# a78-simple-epi.net
KiCad netlist of a schematic drawn in EAGLE
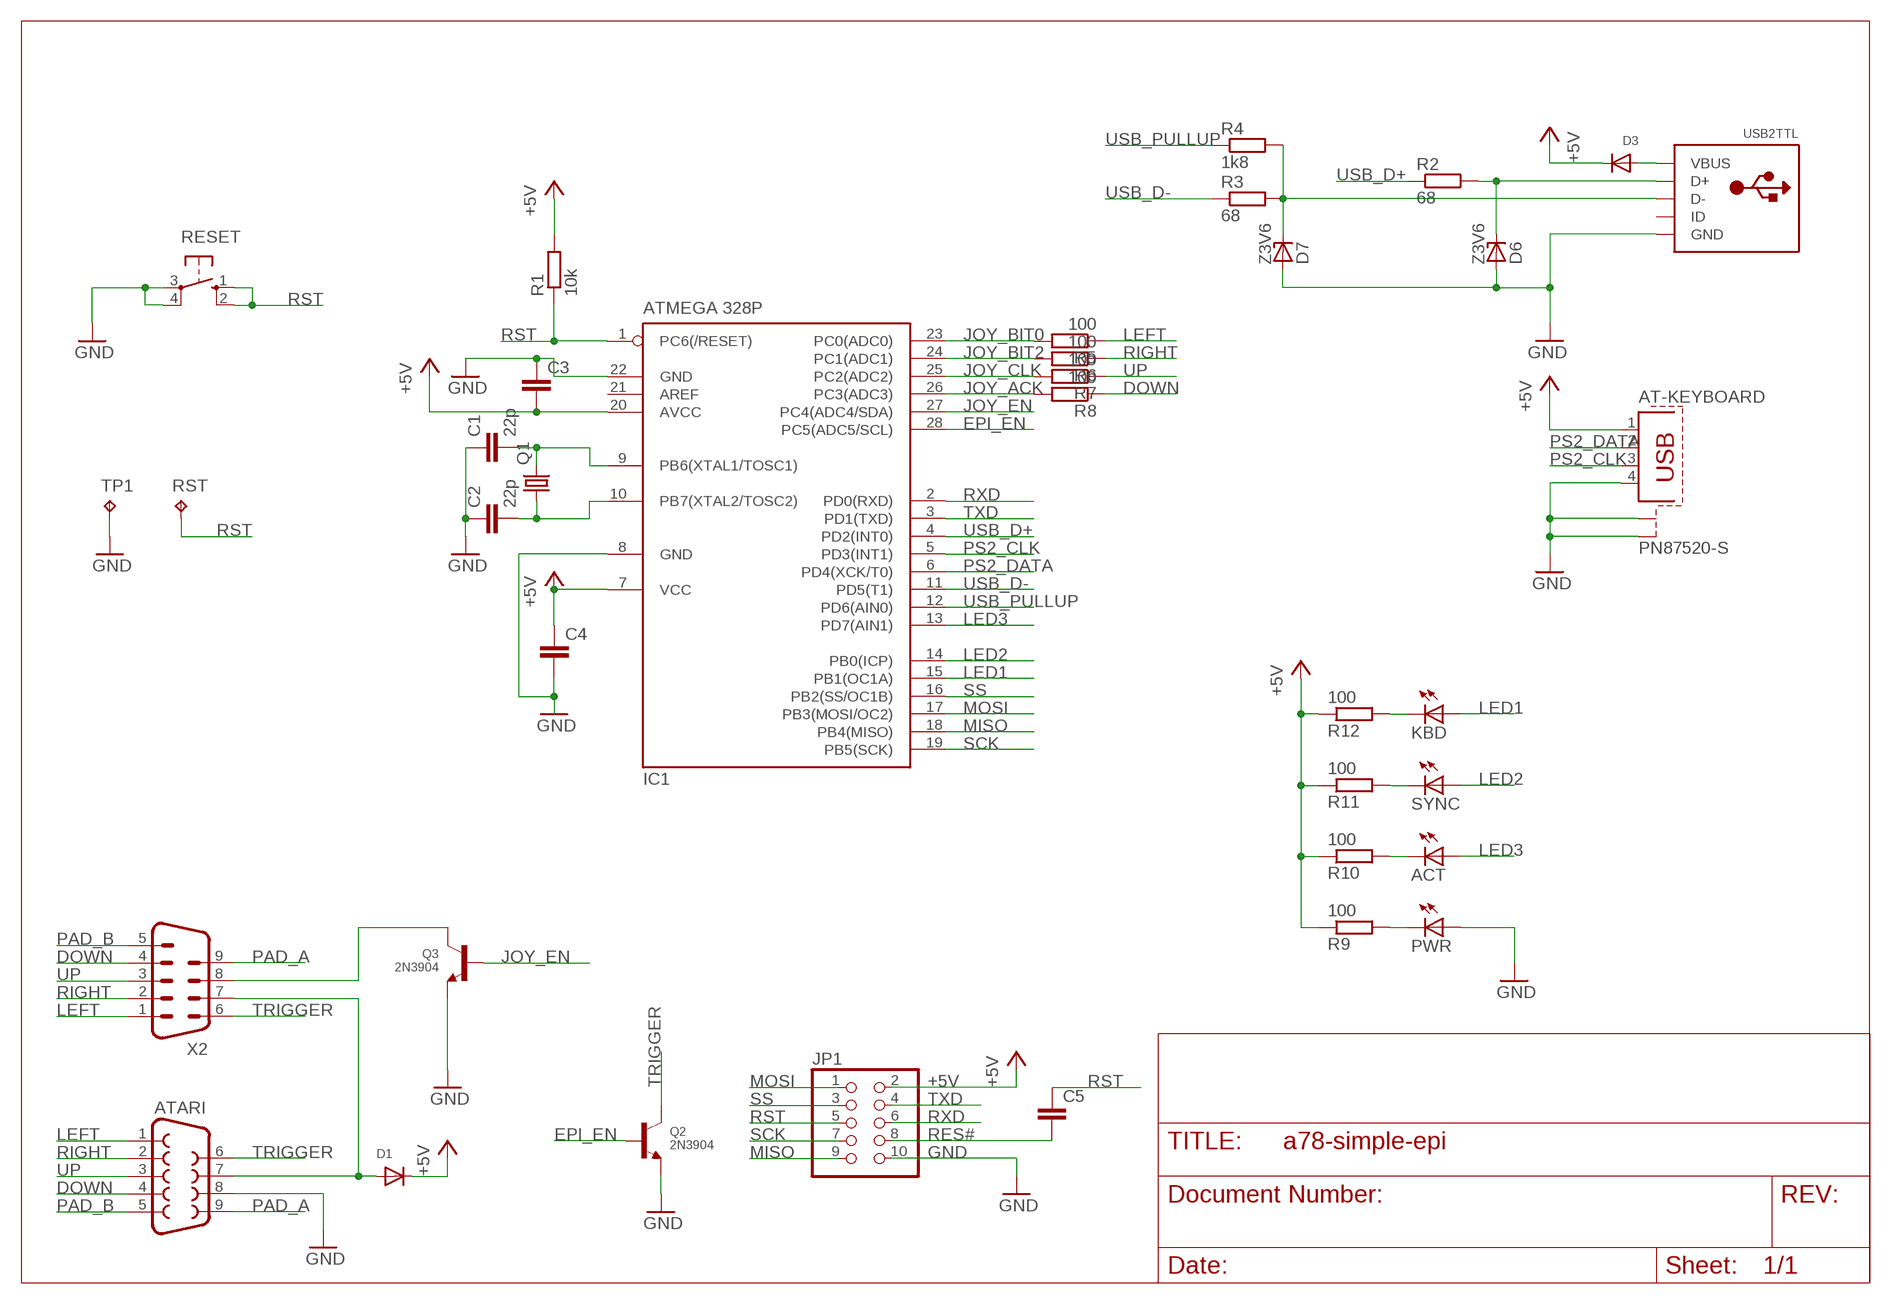
[diagram p0: schematic, sheet 1]

(export (version "E")
  (design (tool "Eeschema 10.0.6"))
  (components
    (comp (ref "ACT")
      (value "LED3MM")
      (footprint "eagle-import:LED3MM")
      (libsource (lib "eagle-import") (part "LED3MM"))
    )
    (comp (ref "AT-KEYBOARD")
      (value "PN87520-S")
      (footprint "eagle-import:PN87520-S")
      (libsource (lib "eagle-import") (part "PN87520-S"))
    )
    (comp (ref "ATARI")
      (value "F09D")
      (footprint "eagle-import:F09D")
      (libsource (lib "eagle-import") (part "F09D"))
    )
    (comp (ref "C1")
      (value "22p")
      (footprint "eagle-import:C0603")
      (libsource (lib "eagle-import") (part "C-EUC0603"))
    )
    (comp (ref "C2")
      (value "22p")
      (footprint "eagle-import:C0603")
      (libsource (lib "eagle-import") (part "C-EUC0603"))
    )
    (comp (ref "C3")
      (value "C-EUC0603")
      (footprint "eagle-import:C0603")
      (libsource (lib "eagle-import") (part "C-EUC0603"))
    )
    (comp (ref "C4")
      (value "C-EUC0603")
      (footprint "eagle-import:C0603")
      (libsource (lib "eagle-import") (part "C-EUC0603"))
    )
    (comp (ref "C5")
      (value "C-EUC0603")
      (footprint "eagle-import:C0603")
      (libsource (lib "eagle-import") (part "C-EUC0603"))
    )
    (comp (ref "D1")
      (value "DIODESOD-323F")
      (footprint "eagle-import:SOD-323F")
      (libsource (lib "eagle-import") (part "DIODESOD-323F"))
    )
    (comp (ref "D3")
      (value "DIODESOD-323F")
      (footprint "eagle-import:SOD-323F")
      (libsource (lib "eagle-import") (part "DIODESOD-323F"))
    )
    (comp (ref "D6")
      (value "Z3V6")
      (footprint "eagle-import:SOT23")
      (libsource (lib "eagle-import") (part "ZENER-DIODESOT23"))
    )
    (comp (ref "D7")
      (value "Z3V6")
      (footprint "eagle-import:SOT23")
      (libsource (lib "eagle-import") (part "ZENER-DIODESOT23"))
    )
    (comp (ref "IC1")
      (value "ATMEGA 328P")
      (footprint "eagle-import:DIL28-3")
      (libsource (lib "eagle-import") (part "MEGA8-P"))
    )
    (comp (ref "JP1")
      (value "PINHD-2X5")
      (footprint "eagle-import:2X05")
      (libsource (lib "eagle-import") (part "PINHD-2X5"))
    )
    (comp (ref "KBD")
      (value "LED3MM")
      (footprint "eagle-import:LED3MM")
      (libsource (lib "eagle-import") (part "LED3MM"))
    )
    (comp (ref "PWR")
      (value "LED3MM")
      (footprint "eagle-import:LED3MM")
      (libsource (lib "eagle-import") (part "LED3MM"))
    )
    (comp (ref "Q1")
      (value "CRYSTALHC49S")
      (footprint "eagle-import:HC49S")
      (libsource (lib "eagle-import") (part "CRYSTALHC49S"))
    )
    (comp (ref "Q2")
      (value "2N3904")
      (footprint "eagle-import:SOT23-R")
      (libsource (lib "eagle-import") (part "TRANSISTOR_NPN"))
    )
    (comp (ref "Q3")
      (value "2N3904")
      (footprint "eagle-import:SOT23-R")
      (libsource (lib "eagle-import") (part "TRANSISTOR_NPN"))
    )
    (comp (ref "R1")
      (value "10k")
      (footprint "eagle-import:R0603")
      (libsource (lib "eagle-import") (part "R-EU_R0603"))
    )
    (comp (ref "R2")
      (value "68")
      (footprint "eagle-import:R0603")
      (libsource (lib "eagle-import") (part "R-EU_R0603"))
    )
    (comp (ref "R3")
      (value "68")
      (footprint "eagle-import:R0603")
      (libsource (lib "eagle-import") (part "R-EU_R0603"))
    )
    (comp (ref "R4")
      (value "1k8")
      (footprint "eagle-import:R0603")
      (libsource (lib "eagle-import") (part "R-EU_R0603"))
    )
    (comp (ref "R5")
      (value "100")
      (footprint "eagle-import:R0603")
      (libsource (lib "eagle-import") (part "R-EU_R0603"))
    )
    (comp (ref "R6")
      (value "100")
      (footprint "eagle-import:R0603")
      (libsource (lib "eagle-import") (part "R-EU_R0603"))
    )
    (comp (ref "R7")
      (value "100")
      (footprint "eagle-import:R0603")
      (libsource (lib "eagle-import") (part "R-EU_R0603"))
    )
    (comp (ref "R8")
      (value "100")
      (footprint "eagle-import:R0603")
      (libsource (lib "eagle-import") (part "R-EU_R0603"))
    )
    (comp (ref "R9")
      (value "100")
      (footprint "eagle-import:R0603")
      (libsource (lib "eagle-import") (part "R-EU_R0603"))
    )
    (comp (ref "R10")
      (value "100")
      (footprint "eagle-import:R0603")
      (libsource (lib "eagle-import") (part "R-EU_R0603"))
    )
    (comp (ref "R11")
      (value "100")
      (footprint "eagle-import:R0603")
      (libsource (lib "eagle-import") (part "R-EU_R0603"))
    )
    (comp (ref "R12")
      (value "100")
      (footprint "eagle-import:R0603")
      (libsource (lib "eagle-import") (part "R-EU_R0603"))
    )
    (comp (ref "RESET")
      (value "10-XX")
      (footprint "eagle-import:B3F-10XX")
      (fields (field (name "MPN") "B3F-1000"))
      (libsource (lib "eagle-import") (part "10-XX"))
    )
    (comp (ref "RST")
      (value "TPB1,27")
      (footprint "eagle-import:B1,27")
      (libsource (lib "eagle-import") (part "TPB1,27"))
    )
    (comp (ref "SYNC")
      (value "LED3MM")
      (footprint "eagle-import:LED3MM")
      (libsource (lib "eagle-import") (part "LED3MM"))
    )
    (comp (ref "TP1")
      (value "TPB1,27")
      (footprint "eagle-import:B1,27")
      (libsource (lib "eagle-import") (part "TPB1,27"))
    )
    (comp (ref "USB2TTL")
      (value "USBMINIB")
      (footprint "eagle-import:USB-MINIB")
      (libsource (lib "eagle-import") (part "USBMINIB"))
    )
    (comp (ref "X2")
      (value "M09D")
      (footprint "eagle-import:M09D")
      (libsource (lib "eagle-import") (part "M09D"))
    )
  )
  (nets
    (net (code "1") (name "+5V") (class "Default")
      (node (ref "AT-KEYBOARD") (pin "1") (pinfunction "1_1") (pintype "passive"))
      (node (ref "C3") (pin "2") (pinfunction "2_2") (pintype "passive"))
      (node (ref "C4") (pin "1") (pinfunction "1_1") (pintype "passive"))
      (node (ref "D1") (pin "C") (pinfunction "C_C") (pintype "passive"))
      (node (ref "D3") (pin "C") (pinfunction "C_C") (pintype "passive"))
      (node (ref "IC1") (pin "20") (pinfunction "AVCC_20") (pintype "power_in"))
      (node (ref "IC1") (pin "7") (pinfunction "VCC_7") (pintype "power_in"))
      (node (ref "JP1") (pin "2") (pinfunction "2_2") (pintype "passive"))
      (node (ref "R1") (pin "2") (pinfunction "2_2") (pintype "passive"))
      (node (ref "R10") (pin "1") (pinfunction "1_1") (pintype "passive"))
      (node (ref "R11") (pin "1") (pinfunction "1_1") (pintype "passive"))
      (node (ref "R12") (pin "1") (pinfunction "1_1") (pintype "passive"))
      (node (ref "R9") (pin "1") (pinfunction "1_1") (pintype "passive"))
    )
    (net (code "2") (name "/DOWN") (class "Default")
      (node (ref "ATARI") (pin "4") (pinfunction "4_4") (pintype "passive"))
      (node (ref "R8") (pin "1") (pinfunction "1_1") (pintype "passive"))
      (node (ref "X2") (pin "4") (pinfunction "4_4") (pintype "passive"))
    )
    (net (code "3") (name "/EPI_EN") (class "Default")
      (node (ref "IC1") (pin "28") (pinfunction "PC5(ADC5/SCL)_28") (pintype "bidirectional"))
      (node (ref "Q2") (pin "1") (pinfunction "B_1") (pintype "passive"))
    )
    (net (code "4") (name "/JOY_ACK") (class "Default")
      (node (ref "IC1") (pin "26") (pinfunction "PC3(ADC3)_26") (pintype "bidirectional"))
      (node (ref "R8") (pin "2") (pinfunction "2_2") (pintype "passive"))
    )
    (net (code "5") (name "/JOY_BIT0") (class "Default")
      (node (ref "IC1") (pin "23") (pinfunction "PC0(ADC0)_23") (pintype "bidirectional"))
      (node (ref "R5") (pin "2") (pinfunction "2_2") (pintype "passive"))
    )
    (net (code "6") (name "/JOY_BIT2") (class "Default")
      (node (ref "IC1") (pin "24") (pinfunction "PC1(ADC1)_24") (pintype "bidirectional"))
      (node (ref "R6") (pin "2") (pinfunction "2_2") (pintype "passive"))
    )
    (net (code "7") (name "/JOY_CLK") (class "Default")
      (node (ref "IC1") (pin "25") (pinfunction "PC2(ADC2)_25") (pintype "bidirectional"))
      (node (ref "R7") (pin "2") (pinfunction "2_2") (pintype "passive"))
    )
    (net (code "8") (name "/JOY_EN") (class "Default")
      (node (ref "IC1") (pin "27") (pinfunction "PC4(ADC4/SDA)_27") (pintype "bidirectional"))
      (node (ref "Q3") (pin "1") (pinfunction "B_1") (pintype "passive"))
    )
    (net (code "9") (name "/LED1") (class "Default")
      (node (ref "IC1") (pin "15") (pinfunction "PB1(OC1A)_15") (pintype "bidirectional"))
      (node (ref "KBD") (pin "A") (pinfunction "A_A") (pintype "passive"))
    )
    (net (code "10") (name "/LED2") (class "Default")
      (node (ref "IC1") (pin "14") (pinfunction "PB0(ICP)_14") (pintype "bidirectional"))
      (node (ref "SYNC") (pin "A") (pinfunction "A_A") (pintype "passive"))
    )
    (net (code "11") (name "/LED3") (class "Default")
      (node (ref "ACT") (pin "A") (pinfunction "A_A") (pintype "passive"))
      (node (ref "IC1") (pin "13") (pinfunction "PD7(AIN1)_13") (pintype "bidirectional"))
    )
    (net (code "12") (name "/LEFT") (class "Default")
      (node (ref "ATARI") (pin "1") (pinfunction "1_1") (pintype "passive"))
      (node (ref "R5") (pin "1") (pinfunction "1_1") (pintype "passive"))
      (node (ref "X2") (pin "1") (pinfunction "1_1") (pintype "passive"))
    )
    (net (code "13") (name "/MISO") (class "Default")
      (node (ref "IC1") (pin "18") (pinfunction "PB4(MISO)_18") (pintype "bidirectional"))
      (node (ref "JP1") (pin "9") (pinfunction "9_9") (pintype "passive"))
    )
    (net (code "14") (name "/MOSI") (class "Default")
      (node (ref "IC1") (pin "17") (pinfunction "PB3(MOSI/OC2)_17") (pintype "bidirectional"))
      (node (ref "JP1") (pin "1") (pinfunction "1_1") (pintype "passive"))
    )
    (net (code "15") (name "/PAD_A") (class "Default")
      (node (ref "ATARI") (pin "9") (pinfunction "9_9") (pintype "passive"))
      (node (ref "X2") (pin "9") (pinfunction "9_9") (pintype "passive"))
    )
    (net (code "16") (name "/PAD_B") (class "Default")
      (node (ref "ATARI") (pin "5") (pinfunction "5_5") (pintype "passive"))
      (node (ref "X2") (pin "5") (pinfunction "5_5") (pintype "passive"))
    )
    (net (code "17") (name "/PS2_CLK") (class "Default")
      (node (ref "AT-KEYBOARD") (pin "3") (pinfunction "3_3") (pintype "passive"))
      (node (ref "IC1") (pin "5") (pinfunction "PD3(INT1)_5") (pintype "bidirectional"))
    )
    (net (code "18") (name "/PS2_DATA") (class "Default")
      (node (ref "AT-KEYBOARD") (pin "2") (pinfunction "2_2") (pintype "passive"))
      (node (ref "IC1") (pin "6") (pinfunction "PD4(XCK/T0)_6") (pintype "bidirectional"))
    )
    (net (code "19") (name "/RES#") (class "Default")
      (node (ref "C5") (pin "2") (pinfunction "2_2") (pintype "passive"))
      (node (ref "JP1") (pin "8") (pinfunction "8_8") (pintype "passive"))
    )
    (net (code "20") (name "/RIGHT") (class "Default")
      (node (ref "ATARI") (pin "2") (pinfunction "2_2") (pintype "passive"))
      (node (ref "R6") (pin "1") (pinfunction "1_1") (pintype "passive"))
      (node (ref "X2") (pin "2") (pinfunction "2_2") (pintype "passive"))
    )
    (net (code "21") (name "/RST") (class "Default")
      (node (ref "C5") (pin "1") (pinfunction "1_1") (pintype "passive"))
      (node (ref "IC1") (pin "1") (pinfunction "PC6(/RESET)_1") (pintype "bidirectional"))
      (node (ref "JP1") (pin "5") (pinfunction "5_5") (pintype "passive"))
      (node (ref "R1") (pin "1") (pinfunction "1_1") (pintype "passive"))
      (node (ref "RESET") (pin "1") (pinfunction "S_1") (pintype "passive"))
      (node (ref "RESET") (pin "2") (pinfunction "S1_2") (pintype "passive"))
      (node (ref "RST") (pin "TP") (pinfunction "TP_TP") (pintype "input"))
    )
    (net (code "22") (name "/RXD") (class "Default")
      (node (ref "IC1") (pin "2") (pinfunction "PD0(RXD)_2") (pintype "bidirectional"))
      (node (ref "JP1") (pin "6") (pinfunction "6_6") (pintype "passive"))
    )
    (net (code "23") (name "/SCK") (class "Default")
      (node (ref "IC1") (pin "19") (pinfunction "PB5(SCK)_19") (pintype "bidirectional"))
      (node (ref "JP1") (pin "7") (pinfunction "7_7") (pintype "passive"))
    )
    (net (code "24") (name "/SS") (class "Default")
      (node (ref "IC1") (pin "16") (pinfunction "PB2(SS/OC1B)_16") (pintype "bidirectional"))
      (node (ref "JP1") (pin "3") (pinfunction "3_3") (pintype "passive"))
    )
    (net (code "25") (name "/TRIGGER") (class "Default")
      (node (ref "ATARI") (pin "6") (pinfunction "6_6") (pintype "passive"))
      (node (ref "Q2") (pin "3") (pinfunction "C_3") (pintype "passive"))
      (node (ref "X2") (pin "6") (pinfunction "6_6") (pintype "passive"))
    )
    (net (code "26") (name "/TXD") (class "Default")
      (node (ref "IC1") (pin "3") (pinfunction "PD1(TXD)_3") (pintype "bidirectional"))
      (node (ref "JP1") (pin "4") (pinfunction "4_4") (pintype "passive"))
    )
    (net (code "27") (name "/UP") (class "Default")
      (node (ref "ATARI") (pin "3") (pinfunction "3_3") (pintype "passive"))
      (node (ref "R7") (pin "1") (pinfunction "1_1") (pintype "passive"))
      (node (ref "X2") (pin "3") (pinfunction "3_3") (pintype "passive"))
    )
    (net (code "28") (name "/USB_D+") (class "Default")
      (node (ref "IC1") (pin "4") (pinfunction "PD2(INT0)_4") (pintype "bidirectional"))
      (node (ref "R2") (pin "1") (pinfunction "1_1") (pintype "passive"))
    )
    (net (code "29") (name "/USB_D-") (class "Default")
      (node (ref "IC1") (pin "11") (pinfunction "PD5(T1)_11") (pintype "bidirectional"))
      (node (ref "R3") (pin "1") (pinfunction "1_1") (pintype "passive"))
    )
    (net (code "30") (name "/USB_PULLUP") (class "Default")
      (node (ref "IC1") (pin "12") (pinfunction "PD6(AIN0)_12") (pintype "bidirectional"))
      (node (ref "R4") (pin "1") (pinfunction "1_1") (pintype "passive"))
    )
    (net (code "31") (name "GND") (class "Default")
      (node (ref "AT-KEYBOARD") (pin "4") (pinfunction "4_4") (pintype "passive"))
      (node (ref "AT-KEYBOARD") (pin "S1") (pinfunction "S1_S1") (pintype "passive"))
      (node (ref "AT-KEYBOARD") (pin "S2") (pinfunction "S2_S2") (pintype "passive"))
      (node (ref "ATARI") (pin "8") (pinfunction "8_8") (pintype "passive"))
      (node (ref "C1") (pin "1") (pinfunction "1_1") (pintype "passive"))
      (node (ref "C2") (pin "1") (pinfunction "1_1") (pintype "passive"))
      (node (ref "C3") (pin "1") (pinfunction "1_1") (pintype "passive"))
      (node (ref "C4") (pin "2") (pinfunction "2_2") (pintype "passive"))
      (node (ref "D6") (pin "1") (pinfunction "A_1") (pintype "passive"))
      (node (ref "D7") (pin "1") (pinfunction "A_1") (pintype "passive"))
      (node (ref "IC1") (pin "22") (pinfunction "GND_22") (pintype "power_in"))
      (node (ref "IC1") (pin "8") (pinfunction "GND_8") (pintype "power_in"))
      (node (ref "JP1") (pin "10") (pinfunction "10_10") (pintype "passive"))
      (node (ref "PWR") (pin "A") (pinfunction "A_A") (pintype "passive"))
      (node (ref "Q2") (pin "2") (pinfunction "E_2") (pintype "passive"))
      (node (ref "Q3") (pin "2") (pinfunction "E_2") (pintype "passive"))
      (node (ref "RESET") (pin "3") (pinfunction "P_3") (pintype "passive"))
      (node (ref "RESET") (pin "4") (pinfunction "P1_4") (pintype "passive"))
      (node (ref "TP1") (pin "TP") (pinfunction "TP_TP") (pintype "input"))
      (node (ref "USB2TTL") (pin "GND") (pinfunction "GND_GND") (pintype "power_in"))
    )
    (net (code "32") (name "Net-(ACT-C)") (class "Default")
      (node (ref "ACT") (pin "K") (pinfunction "C_K") (pintype "passive"))
      (node (ref "R10") (pin "2") (pinfunction "2_2") (pintype "passive"))
    )
    (net (code "33") (name "Net-(ATARI-Pad7)") (class "Default")
      (node (ref "ATARI") (pin "7") (pinfunction "7_7") (pintype "passive"))
      (node (ref "D1") (pin "A") (pinfunction "A_A") (pintype "passive"))
      (node (ref "X2") (pin "7") (pinfunction "7_7") (pintype "passive"))
    )
    (net (code "34") (name "Net-(D3-PadA)") (class "Default")
      (node (ref "D3") (pin "A") (pinfunction "A_A") (pintype "passive"))
      (node (ref "USB2TTL") (pin "VBUS") (pinfunction "VBUS_VBUS") (pintype "power_in"))
    )
    (net (code "35") (name "Net-(D6-C)") (class "Default")
      (node (ref "D6") (pin "3") (pinfunction "C_3") (pintype "passive"))
      (node (ref "R2") (pin "2") (pinfunction "2_2") (pintype "passive"))
      (node (ref "USB2TTL") (pin "D+") (pinfunction "D+_D+") (pintype "bidirectional"))
    )
    (net (code "36") (name "Net-(D7-C)") (class "Default")
      (node (ref "D7") (pin "3") (pinfunction "C_3") (pintype "passive"))
      (node (ref "R3") (pin "2") (pinfunction "2_2") (pintype "passive"))
      (node (ref "R4") (pin "2") (pinfunction "2_2") (pintype "passive"))
      (node (ref "USB2TTL") (pin "D-") (pinfunction "D-_D-") (pintype "bidirectional"))
    )
    (net (code "37") (name "Net-(IC1-PB6(XTAL1{slash}TOSC1))") (class "Default")
      (node (ref "C1") (pin "2") (pinfunction "2_2") (pintype "passive"))
      (node (ref "IC1") (pin "9") (pinfunction "PB6(XTAL1/TOSC1)_9") (pintype "bidirectional"))
      (node (ref "Q1") (pin "2") (pinfunction "2_2") (pintype "passive"))
    )
    (net (code "38") (name "Net-(IC1-PB7(XTAL2{slash}TOSC2))") (class "Default")
      (node (ref "C2") (pin "2") (pinfunction "2_2") (pintype "passive"))
      (node (ref "IC1") (pin "10") (pinfunction "PB7(XTAL2/TOSC2)_10") (pintype "bidirectional"))
      (node (ref "Q1") (pin "1") (pinfunction "1_1") (pintype "passive"))
    )
    (net (code "39") (name "Net-(KBD-C)") (class "Default")
      (node (ref "KBD") (pin "K") (pinfunction "C_K") (pintype "passive"))
      (node (ref "R12") (pin "2") (pinfunction "2_2") (pintype "passive"))
    )
    (net (code "40") (name "Net-(PWR-C)") (class "Default")
      (node (ref "PWR") (pin "K") (pinfunction "C_K") (pintype "passive"))
      (node (ref "R9") (pin "2") (pinfunction "2_2") (pintype "passive"))
    )
    (net (code "41") (name "Net-(Q3-C)") (class "Default")
      (node (ref "Q3") (pin "3") (pinfunction "C_3") (pintype "passive"))
      (node (ref "X2") (pin "8") (pinfunction "8_8") (pintype "passive"))
    )
    (net (code "42") (name "Net-(SYNC-C)") (class "Default")
      (node (ref "R11") (pin "2") (pinfunction "2_2") (pintype "passive"))
      (node (ref "SYNC") (pin "K") (pinfunction "C_K") (pintype "passive"))
    )
    (net (code "43") (name "unconnected-(IC1-AREF-Pad21)") (class "Default")
      (node (ref "IC1") (pin "21") (pinfunction "AREF_21") (pintype "passive"))
    )
    (net (code "44") (name "unconnected-(USB2TTL-PadID)") (class "Default")
      (node (ref "USB2TTL") (pin "ID") (pinfunction "ID_ID") (pintype "bidirectional"))
    )
  )
)
